# Sheet1.net
KiCad netlist of a schematic drawn in Altium Designer
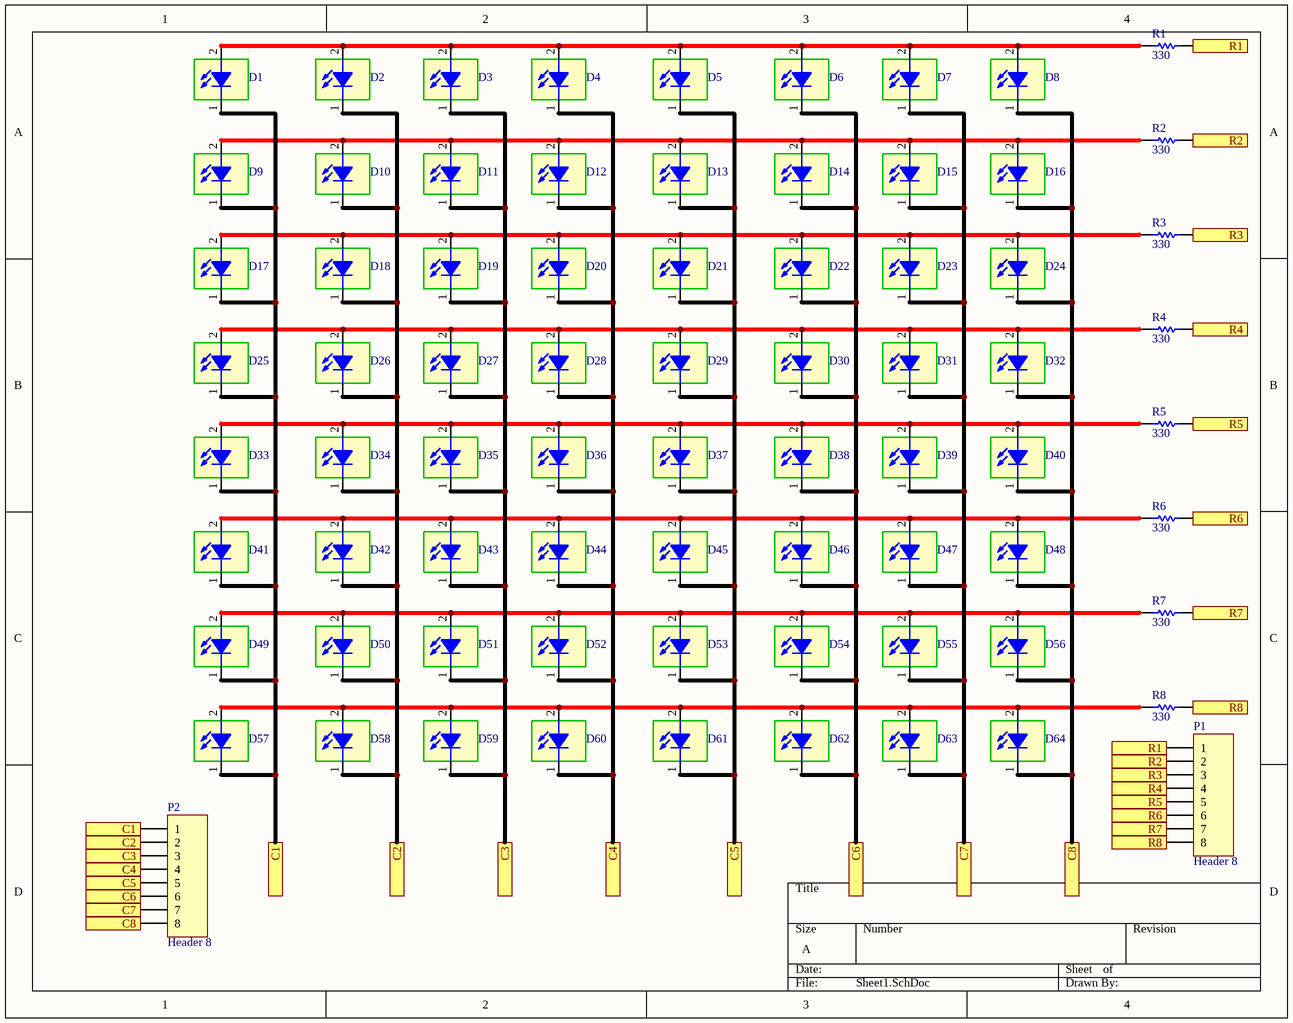
[diagram p0: Sheet1.SchDoc]

(export (version "E")
  (design (tool "Eeschema 10.0.6"))
  (components
    (comp (ref "D1")
      (value "SMD 1206 LED")
      (footprint "LED 1206")
      (libsource (lib "Altium") (part "LED SMD 1206"))
    )
    (comp (ref "D2")
      (value "SMD 1206 LED")
      (footprint "LED 1206")
      (libsource (lib "Altium") (part "LED SMD 1206"))
    )
    (comp (ref "D3")
      (value "SMD 1206 LED")
      (footprint "LED 1206")
      (libsource (lib "Altium") (part "LED SMD 1206"))
    )
    (comp (ref "D4")
      (value "SMD 1206 LED")
      (footprint "LED 1206")
      (libsource (lib "Altium") (part "LED SMD 1206"))
    )
    (comp (ref "D5")
      (value "SMD 1206 LED")
      (footprint "LED 1206")
      (libsource (lib "Altium") (part "LED SMD 1206"))
    )
    (comp (ref "D6")
      (value "SMD 1206 LED")
      (footprint "LED 1206")
      (libsource (lib "Altium") (part "LED SMD 1206"))
    )
    (comp (ref "D7")
      (value "SMD 1206 LED")
      (footprint "LED 1206")
      (libsource (lib "Altium") (part "LED SMD 1206"))
    )
    (comp (ref "D8")
      (value "SMD 1206 LED")
      (footprint "LED 1206")
      (libsource (lib "Altium") (part "LED SMD 1206"))
    )
    (comp (ref "D9")
      (value "SMD 1206 LED")
      (footprint "LED 1206")
      (libsource (lib "Altium") (part "LED SMD 1206"))
    )
    (comp (ref "D10")
      (value "SMD 1206 LED")
      (footprint "LED 1206")
      (libsource (lib "Altium") (part "LED SMD 1206"))
    )
    (comp (ref "D11")
      (value "SMD 1206 LED")
      (footprint "LED 1206")
      (libsource (lib "Altium") (part "LED SMD 1206"))
    )
    (comp (ref "D12")
      (value "SMD 1206 LED")
      (footprint "LED 1206")
      (libsource (lib "Altium") (part "LED SMD 1206"))
    )
    (comp (ref "D13")
      (value "SMD 1206 LED")
      (footprint "LED 1206")
      (libsource (lib "Altium") (part "LED SMD 1206"))
    )
    (comp (ref "D14")
      (value "SMD 1206 LED")
      (footprint "LED 1206")
      (libsource (lib "Altium") (part "LED SMD 1206"))
    )
    (comp (ref "D15")
      (value "SMD 1206 LED")
      (footprint "LED 1206")
      (libsource (lib "Altium") (part "LED SMD 1206"))
    )
    (comp (ref "D16")
      (value "SMD 1206 LED")
      (footprint "LED 1206")
      (libsource (lib "Altium") (part "LED SMD 1206"))
    )
    (comp (ref "D17")
      (value "SMD 1206 LED")
      (footprint "LED 1206")
      (libsource (lib "Altium") (part "LED SMD 1206"))
    )
    (comp (ref "D18")
      (value "SMD 1206 LED")
      (footprint "LED 1206")
      (libsource (lib "Altium") (part "LED SMD 1206"))
    )
    (comp (ref "D19")
      (value "SMD 1206 LED")
      (footprint "LED 1206")
      (libsource (lib "Altium") (part "LED SMD 1206"))
    )
    (comp (ref "D20")
      (value "SMD 1206 LED")
      (footprint "LED 1206")
      (libsource (lib "Altium") (part "LED SMD 1206"))
    )
    (comp (ref "D21")
      (value "SMD 1206 LED")
      (footprint "LED 1206")
      (libsource (lib "Altium") (part "LED SMD 1206"))
    )
    (comp (ref "D22")
      (value "SMD 1206 LED")
      (footprint "LED 1206")
      (libsource (lib "Altium") (part "LED SMD 1206"))
    )
    (comp (ref "D23")
      (value "SMD 1206 LED")
      (footprint "LED 1206")
      (libsource (lib "Altium") (part "LED SMD 1206"))
    )
    (comp (ref "D24")
      (value "SMD 1206 LED")
      (footprint "LED 1206")
      (libsource (lib "Altium") (part "LED SMD 1206"))
    )
    (comp (ref "D25")
      (value "SMD 1206 LED")
      (footprint "LED 1206")
      (libsource (lib "Altium") (part "LED SMD 1206"))
    )
    (comp (ref "D26")
      (value "SMD 1206 LED")
      (footprint "LED 1206")
      (libsource (lib "Altium") (part "LED SMD 1206"))
    )
    (comp (ref "D27")
      (value "SMD 1206 LED")
      (footprint "LED 1206")
      (libsource (lib "Altium") (part "LED SMD 1206"))
    )
    (comp (ref "D28")
      (value "SMD 1206 LED")
      (footprint "LED 1206")
      (libsource (lib "Altium") (part "LED SMD 1206"))
    )
    (comp (ref "D29")
      (value "SMD 1206 LED")
      (footprint "LED 1206")
      (libsource (lib "Altium") (part "LED SMD 1206"))
    )
    (comp (ref "D30")
      (value "SMD 1206 LED")
      (footprint "LED 1206")
      (libsource (lib "Altium") (part "LED SMD 1206"))
    )
    (comp (ref "D31")
      (value "SMD 1206 LED")
      (footprint "LED 1206")
      (libsource (lib "Altium") (part "LED SMD 1206"))
    )
    (comp (ref "D32")
      (value "SMD 1206 LED")
      (footprint "LED 1206")
      (libsource (lib "Altium") (part "LED SMD 1206"))
    )
    (comp (ref "D33")
      (value "SMD 1206 LED")
      (footprint "LED 1206")
      (libsource (lib "Altium") (part "LED SMD 1206"))
    )
    (comp (ref "D34")
      (value "SMD 1206 LED")
      (footprint "LED 1206")
      (libsource (lib "Altium") (part "LED SMD 1206"))
    )
    (comp (ref "D35")
      (value "SMD 1206 LED")
      (footprint "LED 1206")
      (libsource (lib "Altium") (part "LED SMD 1206"))
    )
    (comp (ref "D36")
      (value "SMD 1206 LED")
      (footprint "LED 1206")
      (libsource (lib "Altium") (part "LED SMD 1206"))
    )
    (comp (ref "D37")
      (value "SMD 1206 LED")
      (footprint "LED 1206")
      (libsource (lib "Altium") (part "LED SMD 1206"))
    )
    (comp (ref "D38")
      (value "SMD 1206 LED")
      (footprint "LED 1206")
      (libsource (lib "Altium") (part "LED SMD 1206"))
    )
    (comp (ref "D39")
      (value "SMD 1206 LED")
      (footprint "LED 1206")
      (libsource (lib "Altium") (part "LED SMD 1206"))
    )
    (comp (ref "D40")
      (value "SMD 1206 LED")
      (footprint "LED 1206")
      (libsource (lib "Altium") (part "LED SMD 1206"))
    )
    (comp (ref "D41")
      (value "SMD 1206 LED")
      (footprint "LED 1206")
      (libsource (lib "Altium") (part "LED SMD 1206"))
    )
    (comp (ref "D42")
      (value "SMD 1206 LED")
      (footprint "LED 1206")
      (libsource (lib "Altium") (part "LED SMD 1206"))
    )
    (comp (ref "D43")
      (value "SMD 1206 LED")
      (footprint "LED 1206")
      (libsource (lib "Altium") (part "LED SMD 1206"))
    )
    (comp (ref "D44")
      (value "SMD 1206 LED")
      (footprint "LED 1206")
      (libsource (lib "Altium") (part "LED SMD 1206"))
    )
    (comp (ref "D45")
      (value "SMD 1206 LED")
      (footprint "LED 1206")
      (libsource (lib "Altium") (part "LED SMD 1206"))
    )
    (comp (ref "D46")
      (value "SMD 1206 LED")
      (footprint "LED 1206")
      (libsource (lib "Altium") (part "LED SMD 1206"))
    )
    (comp (ref "D47")
      (value "SMD 1206 LED")
      (footprint "LED 1206")
      (libsource (lib "Altium") (part "LED SMD 1206"))
    )
    (comp (ref "D48")
      (value "SMD 1206 LED")
      (footprint "LED 1206")
      (libsource (lib "Altium") (part "LED SMD 1206"))
    )
    (comp (ref "D49")
      (value "SMD 1206 LED")
      (footprint "LED 1206")
      (libsource (lib "Altium") (part "LED SMD 1206"))
    )
    (comp (ref "D50")
      (value "SMD 1206 LED")
      (footprint "LED 1206")
      (libsource (lib "Altium") (part "LED SMD 1206"))
    )
    (comp (ref "D51")
      (value "SMD 1206 LED")
      (footprint "LED 1206")
      (libsource (lib "Altium") (part "LED SMD 1206"))
    )
    (comp (ref "D52")
      (value "SMD 1206 LED")
      (footprint "LED 1206")
      (libsource (lib "Altium") (part "LED SMD 1206"))
    )
    (comp (ref "D53")
      (value "SMD 1206 LED")
      (footprint "LED 1206")
      (libsource (lib "Altium") (part "LED SMD 1206"))
    )
    (comp (ref "D54")
      (value "SMD 1206 LED")
      (footprint "LED 1206")
      (libsource (lib "Altium") (part "LED SMD 1206"))
    )
    (comp (ref "D55")
      (value "SMD 1206 LED")
      (footprint "LED 1206")
      (libsource (lib "Altium") (part "LED SMD 1206"))
    )
    (comp (ref "D56")
      (value "SMD 1206 LED")
      (footprint "LED 1206")
      (libsource (lib "Altium") (part "LED SMD 1206"))
    )
    (comp (ref "D57")
      (value "SMD 1206 LED")
      (footprint "LED 1206")
      (libsource (lib "Altium") (part "LED SMD 1206"))
    )
    (comp (ref "D58")
      (value "SMD 1206 LED")
      (footprint "LED 1206")
      (libsource (lib "Altium") (part "LED SMD 1206"))
    )
    (comp (ref "D59")
      (value "SMD 1206 LED")
      (footprint "LED 1206")
      (libsource (lib "Altium") (part "LED SMD 1206"))
    )
    (comp (ref "D60")
      (value "SMD 1206 LED")
      (footprint "LED 1206")
      (libsource (lib "Altium") (part "LED SMD 1206"))
    )
    (comp (ref "D61")
      (value "SMD 1206 LED")
      (footprint "LED 1206")
      (libsource (lib "Altium") (part "LED SMD 1206"))
    )
    (comp (ref "D62")
      (value "SMD 1206 LED")
      (footprint "LED 1206")
      (libsource (lib "Altium") (part "LED SMD 1206"))
    )
    (comp (ref "D63")
      (value "SMD 1206 LED")
      (footprint "LED 1206")
      (libsource (lib "Altium") (part "LED SMD 1206"))
    )
    (comp (ref "D64")
      (value "SMD 1206 LED")
      (footprint "LED 1206")
      (libsource (lib "Altium") (part "LED SMD 1206"))
    )
    (comp (ref "P1")
      (value "Header 8")
      (footprint "HDR1X8")
      (description "Header, 8-Pin")
      (fields (field (name "PUBLISHER") "Altium Limited"))
      (libsource (lib "Altium") (part "Header 8"))
    )
    (comp (ref "P2")
      (value "Header 8")
      (footprint "HDR1X8")
      (description "Header, 8-Pin")
      (fields (field (name "PUBLISHER") "Altium Limited"))
      (libsource (lib "Altium") (part "Header 8"))
    )
    (comp (ref "R1")
      (value "330")
      (footprint "RES1206")
      (description "TOTAL SMD RESISTOR PACK")
      (fields (field (name "DESIGNER") "Abbas Basereh"))
      (libsource (lib "Altium") (part "RES SMD PACKAGE"))
    )
    (comp (ref "R2")
      (value "330")
      (footprint "RES1206")
      (description "TOTAL SMD RESISTOR PACK")
      (fields (field (name "DESIGNER") "Abbas Basereh"))
      (libsource (lib "Altium") (part "RES SMD PACKAGE"))
    )
    (comp (ref "R3")
      (value "330")
      (footprint "RES1206")
      (description "TOTAL SMD RESISTOR PACK")
      (fields (field (name "DESIGNER") "Abbas Basereh"))
      (libsource (lib "Altium") (part "RES SMD PACKAGE"))
    )
    (comp (ref "R4")
      (value "330")
      (footprint "RES1206")
      (description "TOTAL SMD RESISTOR PACK")
      (fields (field (name "DESIGNER") "Abbas Basereh"))
      (libsource (lib "Altium") (part "RES SMD PACKAGE"))
    )
    (comp (ref "R5")
      (value "330")
      (footprint "RES1206")
      (description "TOTAL SMD RESISTOR PACK")
      (fields (field (name "DESIGNER") "Abbas Basereh"))
      (libsource (lib "Altium") (part "RES SMD PACKAGE"))
    )
    (comp (ref "R6")
      (value "330")
      (footprint "RES1206")
      (description "TOTAL SMD RESISTOR PACK")
      (fields (field (name "DESIGNER") "Abbas Basereh"))
      (libsource (lib "Altium") (part "RES SMD PACKAGE"))
    )
    (comp (ref "R7")
      (value "330")
      (footprint "RES1206")
      (description "TOTAL SMD RESISTOR PACK")
      (fields (field (name "DESIGNER") "Abbas Basereh"))
      (libsource (lib "Altium") (part "RES SMD PACKAGE"))
    )
    (comp (ref "R8")
      (value "330")
      (footprint "RES1206")
      (description "TOTAL SMD RESISTOR PACK")
      (fields (field (name "DESIGNER") "Abbas Basereh"))
      (libsource (lib "Altium") (part "RES SMD PACKAGE"))
    )
  )
  (nets
    (net (code "1") (name "/C1") (class "Default")
      (node (ref "D1") (pin "1") (pinfunction "1_1") (pintype "passive"))
      (node (ref "D17") (pin "1") (pinfunction "1_1") (pintype "passive"))
      (node (ref "D25") (pin "1") (pinfunction "1_1") (pintype "passive"))
      (node (ref "D33") (pin "1") (pinfunction "1_1") (pintype "passive"))
      (node (ref "D41") (pin "1") (pinfunction "1_1") (pintype "passive"))
      (node (ref "D49") (pin "1") (pinfunction "1_1") (pintype "passive"))
      (node (ref "D57") (pin "1") (pinfunction "1_1") (pintype "passive"))
      (node (ref "D9") (pin "1") (pinfunction "1_1") (pintype "passive"))
      (node (ref "P2") (pin "1") (pinfunction "1_1") (pintype "passive"))
    )
    (net (code "2") (name "/C2") (class "Default")
      (node (ref "D10") (pin "1") (pinfunction "1_1") (pintype "passive"))
      (node (ref "D18") (pin "1") (pinfunction "1_1") (pintype "passive"))
      (node (ref "D2") (pin "1") (pinfunction "1_1") (pintype "passive"))
      (node (ref "D26") (pin "1") (pinfunction "1_1") (pintype "passive"))
      (node (ref "D34") (pin "1") (pinfunction "1_1") (pintype "passive"))
      (node (ref "D42") (pin "1") (pinfunction "1_1") (pintype "passive"))
      (node (ref "D50") (pin "1") (pinfunction "1_1") (pintype "passive"))
      (node (ref "D58") (pin "1") (pinfunction "1_1") (pintype "passive"))
      (node (ref "P2") (pin "2") (pinfunction "2_2") (pintype "passive"))
    )
    (net (code "3") (name "/C3") (class "Default")
      (node (ref "D11") (pin "1") (pinfunction "1_1") (pintype "passive"))
      (node (ref "D19") (pin "1") (pinfunction "1_1") (pintype "passive"))
      (node (ref "D27") (pin "1") (pinfunction "1_1") (pintype "passive"))
      (node (ref "D3") (pin "1") (pinfunction "1_1") (pintype "passive"))
      (node (ref "D35") (pin "1") (pinfunction "1_1") (pintype "passive"))
      (node (ref "D43") (pin "1") (pinfunction "1_1") (pintype "passive"))
      (node (ref "D51") (pin "1") (pinfunction "1_1") (pintype "passive"))
      (node (ref "D59") (pin "1") (pinfunction "1_1") (pintype "passive"))
      (node (ref "P2") (pin "3") (pinfunction "3_3") (pintype "passive"))
    )
    (net (code "4") (name "/C4") (class "Default")
      (node (ref "D12") (pin "1") (pinfunction "1_1") (pintype "passive"))
      (node (ref "D20") (pin "1") (pinfunction "1_1") (pintype "passive"))
      (node (ref "D28") (pin "1") (pinfunction "1_1") (pintype "passive"))
      (node (ref "D36") (pin "1") (pinfunction "1_1") (pintype "passive"))
      (node (ref "D4") (pin "1") (pinfunction "1_1") (pintype "passive"))
      (node (ref "D44") (pin "1") (pinfunction "1_1") (pintype "passive"))
      (node (ref "D52") (pin "1") (pinfunction "1_1") (pintype "passive"))
      (node (ref "D60") (pin "1") (pinfunction "1_1") (pintype "passive"))
      (node (ref "P2") (pin "4") (pinfunction "4_4") (pintype "passive"))
    )
    (net (code "5") (name "/C5") (class "Default")
      (node (ref "D13") (pin "1") (pinfunction "1_1") (pintype "passive"))
      (node (ref "D21") (pin "1") (pinfunction "1_1") (pintype "passive"))
      (node (ref "D29") (pin "1") (pinfunction "1_1") (pintype "passive"))
      (node (ref "D37") (pin "1") (pinfunction "1_1") (pintype "passive"))
      (node (ref "D45") (pin "1") (pinfunction "1_1") (pintype "passive"))
      (node (ref "D5") (pin "1") (pinfunction "1_1") (pintype "passive"))
      (node (ref "D53") (pin "1") (pinfunction "1_1") (pintype "passive"))
      (node (ref "D61") (pin "1") (pinfunction "1_1") (pintype "passive"))
      (node (ref "P2") (pin "5") (pinfunction "5_5") (pintype "passive"))
    )
    (net (code "6") (name "/C6") (class "Default")
      (node (ref "D14") (pin "1") (pinfunction "1_1") (pintype "passive"))
      (node (ref "D22") (pin "1") (pinfunction "1_1") (pintype "passive"))
      (node (ref "D30") (pin "1") (pinfunction "1_1") (pintype "passive"))
      (node (ref "D38") (pin "1") (pinfunction "1_1") (pintype "passive"))
      (node (ref "D46") (pin "1") (pinfunction "1_1") (pintype "passive"))
      (node (ref "D54") (pin "1") (pinfunction "1_1") (pintype "passive"))
      (node (ref "D6") (pin "1") (pinfunction "1_1") (pintype "passive"))
      (node (ref "D62") (pin "1") (pinfunction "1_1") (pintype "passive"))
      (node (ref "P2") (pin "6") (pinfunction "6_6") (pintype "passive"))
    )
    (net (code "7") (name "/C7") (class "Default")
      (node (ref "D15") (pin "1") (pinfunction "1_1") (pintype "passive"))
      (node (ref "D23") (pin "1") (pinfunction "1_1") (pintype "passive"))
      (node (ref "D31") (pin "1") (pinfunction "1_1") (pintype "passive"))
      (node (ref "D39") (pin "1") (pinfunction "1_1") (pintype "passive"))
      (node (ref "D47") (pin "1") (pinfunction "1_1") (pintype "passive"))
      (node (ref "D55") (pin "1") (pinfunction "1_1") (pintype "passive"))
      (node (ref "D63") (pin "1") (pinfunction "1_1") (pintype "passive"))
      (node (ref "D7") (pin "1") (pinfunction "1_1") (pintype "passive"))
      (node (ref "P2") (pin "7") (pinfunction "7_7") (pintype "passive"))
    )
    (net (code "8") (name "/C8") (class "Default")
      (node (ref "D16") (pin "1") (pinfunction "1_1") (pintype "passive"))
      (node (ref "D24") (pin "1") (pinfunction "1_1") (pintype "passive"))
      (node (ref "D32") (pin "1") (pinfunction "1_1") (pintype "passive"))
      (node (ref "D40") (pin "1") (pinfunction "1_1") (pintype "passive"))
      (node (ref "D48") (pin "1") (pinfunction "1_1") (pintype "passive"))
      (node (ref "D56") (pin "1") (pinfunction "1_1") (pintype "passive"))
      (node (ref "D64") (pin "1") (pinfunction "1_1") (pintype "passive"))
      (node (ref "D8") (pin "1") (pinfunction "1_1") (pintype "passive"))
      (node (ref "P2") (pin "8") (pinfunction "8_8") (pintype "passive"))
    )
    (net (code "9") (name "/R1") (class "Default")
      (node (ref "P1") (pin "1") (pinfunction "1_1") (pintype "passive"))
      (node (ref "R1") (pin "1") (pinfunction "1_1") (pintype "passive"))
    )
    (net (code "10") (name "/R2") (class "Default")
      (node (ref "P1") (pin "2") (pinfunction "2_2") (pintype "passive"))
      (node (ref "R2") (pin "1") (pinfunction "1_1") (pintype "passive"))
    )
    (net (code "11") (name "/R3") (class "Default")
      (node (ref "P1") (pin "3") (pinfunction "3_3") (pintype "passive"))
      (node (ref "R3") (pin "1") (pinfunction "1_1") (pintype "passive"))
    )
    (net (code "12") (name "/R4") (class "Default")
      (node (ref "P1") (pin "4") (pinfunction "4_4") (pintype "passive"))
      (node (ref "R4") (pin "1") (pinfunction "1_1") (pintype "passive"))
    )
    (net (code "13") (name "/R5") (class "Default")
      (node (ref "P1") (pin "5") (pinfunction "5_5") (pintype "passive"))
      (node (ref "R5") (pin "1") (pinfunction "1_1") (pintype "passive"))
    )
    (net (code "14") (name "/R6") (class "Default")
      (node (ref "P1") (pin "6") (pinfunction "6_6") (pintype "passive"))
      (node (ref "R6") (pin "1") (pinfunction "1_1") (pintype "passive"))
    )
    (net (code "15") (name "/R7") (class "Default")
      (node (ref "P1") (pin "7") (pinfunction "7_7") (pintype "passive"))
      (node (ref "R7") (pin "1") (pinfunction "1_1") (pintype "passive"))
    )
    (net (code "16") (name "/R8") (class "Default")
      (node (ref "P1") (pin "8") (pinfunction "8_8") (pintype "passive"))
      (node (ref "R8") (pin "1") (pinfunction "1_1") (pintype "passive"))
    )
    (net (code "17") (name "Net-(D1-Pad2)") (class "Default")
      (node (ref "D1") (pin "2") (pinfunction "2_2") (pintype "passive"))
      (node (ref "D2") (pin "2") (pinfunction "2_2") (pintype "passive"))
      (node (ref "D3") (pin "2") (pinfunction "2_2") (pintype "passive"))
      (node (ref "D4") (pin "2") (pinfunction "2_2") (pintype "passive"))
      (node (ref "D5") (pin "2") (pinfunction "2_2") (pintype "passive"))
      (node (ref "D6") (pin "2") (pinfunction "2_2") (pintype "passive"))
      (node (ref "D7") (pin "2") (pinfunction "2_2") (pintype "passive"))
      (node (ref "D8") (pin "2") (pinfunction "2_2") (pintype "passive"))
      (node (ref "R1") (pin "2") (pinfunction "2_2") (pintype "passive"))
    )
    (net (code "18") (name "Net-(D10-Pad2)") (class "Default")
      (node (ref "D10") (pin "2") (pinfunction "2_2") (pintype "passive"))
      (node (ref "D11") (pin "2") (pinfunction "2_2") (pintype "passive"))
      (node (ref "D12") (pin "2") (pinfunction "2_2") (pintype "passive"))
      (node (ref "D13") (pin "2") (pinfunction "2_2") (pintype "passive"))
      (node (ref "D14") (pin "2") (pinfunction "2_2") (pintype "passive"))
      (node (ref "D15") (pin "2") (pinfunction "2_2") (pintype "passive"))
      (node (ref "D16") (pin "2") (pinfunction "2_2") (pintype "passive"))
      (node (ref "D9") (pin "2") (pinfunction "2_2") (pintype "passive"))
      (node (ref "R2") (pin "2") (pinfunction "2_2") (pintype "passive"))
    )
    (net (code "19") (name "Net-(D17-Pad2)") (class "Default")
      (node (ref "D17") (pin "2") (pinfunction "2_2") (pintype "passive"))
      (node (ref "D18") (pin "2") (pinfunction "2_2") (pintype "passive"))
      (node (ref "D19") (pin "2") (pinfunction "2_2") (pintype "passive"))
      (node (ref "D20") (pin "2") (pinfunction "2_2") (pintype "passive"))
      (node (ref "D21") (pin "2") (pinfunction "2_2") (pintype "passive"))
      (node (ref "D22") (pin "2") (pinfunction "2_2") (pintype "passive"))
      (node (ref "D23") (pin "2") (pinfunction "2_2") (pintype "passive"))
      (node (ref "D24") (pin "2") (pinfunction "2_2") (pintype "passive"))
      (node (ref "R3") (pin "2") (pinfunction "2_2") (pintype "passive"))
    )
    (net (code "20") (name "Net-(D25-Pad2)") (class "Default")
      (node (ref "D25") (pin "2") (pinfunction "2_2") (pintype "passive"))
      (node (ref "D26") (pin "2") (pinfunction "2_2") (pintype "passive"))
      (node (ref "D27") (pin "2") (pinfunction "2_2") (pintype "passive"))
      (node (ref "D28") (pin "2") (pinfunction "2_2") (pintype "passive"))
      (node (ref "D29") (pin "2") (pinfunction "2_2") (pintype "passive"))
      (node (ref "D30") (pin "2") (pinfunction "2_2") (pintype "passive"))
      (node (ref "D31") (pin "2") (pinfunction "2_2") (pintype "passive"))
      (node (ref "D32") (pin "2") (pinfunction "2_2") (pintype "passive"))
      (node (ref "R4") (pin "2") (pinfunction "2_2") (pintype "passive"))
    )
    (net (code "21") (name "Net-(D33-Pad2)") (class "Default")
      (node (ref "D33") (pin "2") (pinfunction "2_2") (pintype "passive"))
      (node (ref "D34") (pin "2") (pinfunction "2_2") (pintype "passive"))
      (node (ref "D35") (pin "2") (pinfunction "2_2") (pintype "passive"))
      (node (ref "D36") (pin "2") (pinfunction "2_2") (pintype "passive"))
      (node (ref "D37") (pin "2") (pinfunction "2_2") (pintype "passive"))
      (node (ref "D38") (pin "2") (pinfunction "2_2") (pintype "passive"))
      (node (ref "D39") (pin "2") (pinfunction "2_2") (pintype "passive"))
      (node (ref "D40") (pin "2") (pinfunction "2_2") (pintype "passive"))
      (node (ref "R5") (pin "2") (pinfunction "2_2") (pintype "passive"))
    )
    (net (code "22") (name "Net-(D41-Pad2)") (class "Default")
      (node (ref "D41") (pin "2") (pinfunction "2_2") (pintype "passive"))
      (node (ref "D42") (pin "2") (pinfunction "2_2") (pintype "passive"))
      (node (ref "D43") (pin "2") (pinfunction "2_2") (pintype "passive"))
      (node (ref "D44") (pin "2") (pinfunction "2_2") (pintype "passive"))
      (node (ref "D45") (pin "2") (pinfunction "2_2") (pintype "passive"))
      (node (ref "D46") (pin "2") (pinfunction "2_2") (pintype "passive"))
      (node (ref "D47") (pin "2") (pinfunction "2_2") (pintype "passive"))
      (node (ref "D48") (pin "2") (pinfunction "2_2") (pintype "passive"))
      (node (ref "R6") (pin "2") (pinfunction "2_2") (pintype "passive"))
    )
    (net (code "23") (name "Net-(D49-Pad2)") (class "Default")
      (node (ref "D49") (pin "2") (pinfunction "2_2") (pintype "passive"))
      (node (ref "D50") (pin "2") (pinfunction "2_2") (pintype "passive"))
      (node (ref "D51") (pin "2") (pinfunction "2_2") (pintype "passive"))
      (node (ref "D52") (pin "2") (pinfunction "2_2") (pintype "passive"))
      (node (ref "D53") (pin "2") (pinfunction "2_2") (pintype "passive"))
      (node (ref "D54") (pin "2") (pinfunction "2_2") (pintype "passive"))
      (node (ref "D55") (pin "2") (pinfunction "2_2") (pintype "passive"))
      (node (ref "D56") (pin "2") (pinfunction "2_2") (pintype "passive"))
      (node (ref "R7") (pin "2") (pinfunction "2_2") (pintype "passive"))
    )
    (net (code "24") (name "Net-(D57-Pad2)") (class "Default")
      (node (ref "D57") (pin "2") (pinfunction "2_2") (pintype "passive"))
      (node (ref "D58") (pin "2") (pinfunction "2_2") (pintype "passive"))
      (node (ref "D59") (pin "2") (pinfunction "2_2") (pintype "passive"))
      (node (ref "D60") (pin "2") (pinfunction "2_2") (pintype "passive"))
      (node (ref "D61") (pin "2") (pinfunction "2_2") (pintype "passive"))
      (node (ref "D62") (pin "2") (pinfunction "2_2") (pintype "passive"))
      (node (ref "D63") (pin "2") (pinfunction "2_2") (pintype "passive"))
      (node (ref "D64") (pin "2") (pinfunction "2_2") (pintype "passive"))
      (node (ref "R8") (pin "2") (pinfunction "2_2") (pintype "passive"))
    )
  )
)
